# Big_Coil_Gate_Drive_PCBA.net
KiCad netlist of a schematic drawn in Altium Designer
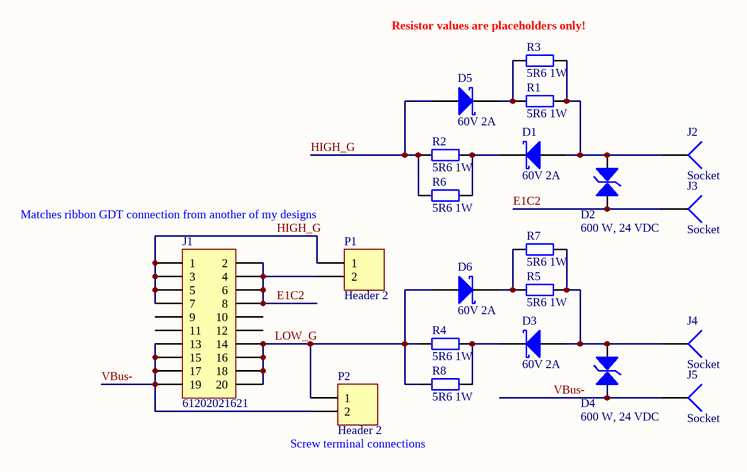
[diagram p0: Big Coil Gate Drive PCBA.SchDoc]

(export (version "E")
  (design (tool "Eeschema 10.0.6"))
  (components
    (comp (ref "D1")
      (value "60V 2A")
      (footprint "DO-214AA_(SMB-J-BEND)_UNI")
      (description "SS26 Schottky rectifier")
      (libsource (lib "TV_Altium_library") (part "SS26"))
    )
    (comp (ref "D2")
      (value "600 W, 24 VDC")
      (footprint "DO-214AA_Bidirectional")
      (description "WE-TVSP Power TVS Diode, bidirectional, 600 W, 24 VDC")
      (fields
        (field (name "PARTNO") "824521241")
        (field (name "MANUFACTURER") "Wurth Elektronik")
        (field (name "CREATED BY") "Baojun Chen")
      )
      (libsource (lib "TV_Altium_library") (part "WE-TVSP DO-214AA, 824521241"))
    )
    (comp (ref "D3")
      (value "60V 2A")
      (footprint "DO-214AA_(SMB-J-BEND)_UNI")
      (description "SS26 Schottky rectifier")
      (libsource (lib "TV_Altium_library") (part "SS26"))
    )
    (comp (ref "D4")
      (value "600 W, 24 VDC")
      (footprint "DO-214AA_Bidirectional")
      (description "WE-TVSP Power TVS Diode, bidirectional, 600 W, 24 VDC")
      (fields
        (field (name "PARTNO") "824521241")
        (field (name "MANUFACTURER") "Wurth Elektronik")
        (field (name "CREATED BY") "Baojun Chen")
      )
      (libsource (lib "TV_Altium_library") (part "WE-TVSP DO-214AA, 824521241"))
    )
    (comp (ref "D5")
      (value "60V 2A")
      (footprint "DO-214AA_(SMB-J-BEND)_UNI")
      (description "SS26 Schottky rectifier")
      (libsource (lib "TV_Altium_library") (part "SS26"))
    )
    (comp (ref "D6")
      (value "60V 2A")
      (footprint "DO-214AA_(SMB-J-BEND)_UNI")
      (description "SS26 Schottky rectifier")
      (libsource (lib "TV_Altium_library") (part "SS26"))
    )
    (comp (ref "J1")
      (value "61202021621")
      (footprint "61202021621")
      (description "WR-BHD 2.54mm Male Box Header")
      (fields (field (name "MANUFACTURER") "Wurth Elektronik") (field (name "CREATED BY") "Baojun Chen"))
      (libsource (lib "TV_Altium_library") (part "61202021621"))
    )
    (comp (ref "J2")
      (value "Socket")
      (footprint "Keystone3534")
      (fields (field (name "PUBLISHER") "Altium Limited"))
      (libsource (lib "Miscellaneous Connectors") (part "Socket"))
    )
    (comp (ref "J3")
      (value "Socket")
      (footprint "Keystone3534")
      (fields (field (name "PUBLISHER") "Altium Limited"))
      (libsource (lib "Miscellaneous Connectors") (part "Socket"))
    )
    (comp (ref "J4")
      (value "Socket")
      (footprint "Keystone3534")
      (fields (field (name "PUBLISHER") "Altium Limited"))
      (libsource (lib "Miscellaneous Connectors") (part "Socket"))
    )
    (comp (ref "J5")
      (value "Socket")
      (footprint "Keystone3534")
      (fields (field (name "PUBLISHER") "Altium Limited"))
      (libsource (lib "Miscellaneous Connectors") (part "Socket"))
    )
    (comp (ref "P1")
      (value "Header 2")
      (footprint "691213510002")
      (description "Header, 2-Pin")
      (fields (field (name "PUBLISHER") "Altium Limited"))
      (libsource (lib "Miscellaneous Connectors") (part "Header 2"))
    )
    (comp (ref "P2")
      (value "Header 2")
      (footprint "691213510002")
      (description "Header, 2-Pin")
      (fields (field (name "PUBLISHER") "Altium Limited"))
      (libsource (lib "Miscellaneous Connectors") (part "Header 2"))
    )
    (comp (ref "R1")
      (value "5R6 1W")
      (description "Resistor")
      (fields (field (name "Comment") "Res2") (field (name "PUBLISHER") "Altium Limited"))
      (libsource (lib "Miscellaneous Devices") (part "Res2"))
    )
    (comp (ref "R2")
      (value "5R6 1W")
      (description "Resistor")
      (fields (field (name "Comment") "Res2") (field (name "PUBLISHER") "Altium Limited"))
      (libsource (lib "Miscellaneous Devices") (part "Res2"))
    )
    (comp (ref "R3")
      (value "5R6 1W")
      (description "Resistor")
      (fields (field (name "Comment") "Res2") (field (name "PUBLISHER") "Altium Limited"))
      (libsource (lib "Miscellaneous Devices") (part "Res2"))
    )
    (comp (ref "R4")
      (value "5R6 1W")
      (description "Resistor")
      (fields (field (name "Comment") "Res2") (field (name "PUBLISHER") "Altium Limited"))
      (libsource (lib "Miscellaneous Devices") (part "Res2"))
    )
    (comp (ref "R5")
      (value "5R6 1W")
      (description "Resistor")
      (fields (field (name "Comment") "Res2") (field (name "PUBLISHER") "Altium Limited"))
      (libsource (lib "Miscellaneous Devices") (part "Res2"))
    )
    (comp (ref "R6")
      (value "5R6 1W")
      (description "Resistor")
      (fields (field (name "Comment") "Res2") (field (name "PUBLISHER") "Altium Limited"))
      (libsource (lib "Miscellaneous Devices") (part "Res2"))
    )
    (comp (ref "R7")
      (value "5R6 1W")
      (description "Resistor")
      (fields (field (name "Comment") "Res2") (field (name "PUBLISHER") "Altium Limited"))
      (libsource (lib "Miscellaneous Devices") (part "Res2"))
    )
    (comp (ref "R8")
      (value "5R6 1W")
      (description "Resistor")
      (fields (field (name "Comment") "Res2") (field (name "PUBLISHER") "Altium Limited"))
      (libsource (lib "Miscellaneous Devices") (part "Res2"))
    )
  )
  (nets
    (net (code "1") (name "/E1C2") (class "Default")
      (node (ref "D2") (pin "2") (pinfunction "2_2") (pintype "passive"))
      (node (ref "J1") (pin "2") (pinfunction "2_2") (pintype "passive"))
      (node (ref "J1") (pin "4") (pinfunction "4_4") (pintype "passive"))
      (node (ref "J1") (pin "6") (pinfunction "6_6") (pintype "passive"))
      (node (ref "J1") (pin "8") (pinfunction "8_8") (pintype "passive"))
      (node (ref "J3") (pin "1") (pinfunction "1_1") (pintype "passive"))
      (node (ref "P1") (pin "2") (pinfunction "2_2") (pintype "passive"))
    )
    (net (code "2") (name "/HIGH_G") (class "Default")
      (node (ref "D5") (pin "A") (pinfunction "A_A") (pintype "passive"))
      (node (ref "J1") (pin "1") (pinfunction "1_1") (pintype "passive"))
      (node (ref "J1") (pin "3") (pinfunction "3_3") (pintype "passive"))
      (node (ref "J1") (pin "5") (pinfunction "5_5") (pintype "passive"))
      (node (ref "J1") (pin "7") (pinfunction "7_7") (pintype "passive"))
      (node (ref "P1") (pin "1") (pinfunction "1_1") (pintype "passive"))
      (node (ref "R2") (pin "1") (pinfunction "1_1") (pintype "passive"))
      (node (ref "R6") (pin "1") (pinfunction "1_1") (pintype "passive"))
    )
    (net (code "3") (name "/LOW_G") (class "Default")
      (node (ref "D6") (pin "A") (pinfunction "A_A") (pintype "passive"))
      (node (ref "J1") (pin "14") (pinfunction "14_14") (pintype "passive"))
      (node (ref "J1") (pin "16") (pinfunction "16_16") (pintype "passive"))
      (node (ref "J1") (pin "18") (pinfunction "18_18") (pintype "passive"))
      (node (ref "J1") (pin "20") (pinfunction "20_20") (pintype "passive"))
      (node (ref "P2") (pin "1") (pinfunction "1_1") (pintype "passive"))
      (node (ref "R4") (pin "1") (pinfunction "1_1") (pintype "passive"))
      (node (ref "R8") (pin "1") (pinfunction "1_1") (pintype "passive"))
    )
    (net (code "4") (name "/VBus-") (class "Default")
      (node (ref "D4") (pin "2") (pinfunction "2_2") (pintype "passive"))
      (node (ref "J1") (pin "13") (pinfunction "13_13") (pintype "passive"))
      (node (ref "J1") (pin "15") (pinfunction "15_15") (pintype "passive"))
      (node (ref "J1") (pin "17") (pinfunction "17_17") (pintype "passive"))
      (node (ref "J1") (pin "19") (pinfunction "19_19") (pintype "passive"))
      (node (ref "J5") (pin "1") (pinfunction "1_1") (pintype "passive"))
      (node (ref "P2") (pin "2") (pinfunction "2_2") (pintype "passive"))
    )
    (net (code "5") (name "Net-(D1-PadA)") (class "Default")
      (node (ref "D1") (pin "A") (pinfunction "A_A") (pintype "passive"))
      (node (ref "D2") (pin "1") (pinfunction "1_1") (pintype "passive"))
      (node (ref "J2") (pin "1") (pinfunction "1_1") (pintype "passive"))
      (node (ref "R1") (pin "2") (pinfunction "2_2") (pintype "passive"))
      (node (ref "R3") (pin "2") (pinfunction "2_2") (pintype "passive"))
    )
    (net (code "6") (name "Net-(D1-PadK)") (class "Default")
      (node (ref "D1") (pin "K") (pinfunction "K_K") (pintype "passive"))
      (node (ref "R2") (pin "2") (pinfunction "2_2") (pintype "passive"))
      (node (ref "R6") (pin "2") (pinfunction "2_2") (pintype "passive"))
    )
    (net (code "7") (name "Net-(D3-PadA)") (class "Default")
      (node (ref "D3") (pin "A") (pinfunction "A_A") (pintype "passive"))
      (node (ref "D4") (pin "1") (pinfunction "1_1") (pintype "passive"))
      (node (ref "J4") (pin "1") (pinfunction "1_1") (pintype "passive"))
      (node (ref "R5") (pin "2") (pinfunction "2_2") (pintype "passive"))
      (node (ref "R7") (pin "2") (pinfunction "2_2") (pintype "passive"))
    )
    (net (code "8") (name "Net-(D3-PadK)") (class "Default")
      (node (ref "D3") (pin "K") (pinfunction "K_K") (pintype "passive"))
      (node (ref "R4") (pin "2") (pinfunction "2_2") (pintype "passive"))
      (node (ref "R8") (pin "2") (pinfunction "2_2") (pintype "passive"))
    )
    (net (code "9") (name "Net-(D5-PadK)") (class "Default")
      (node (ref "D5") (pin "K") (pinfunction "K_K") (pintype "passive"))
      (node (ref "R1") (pin "1") (pinfunction "1_1") (pintype "passive"))
      (node (ref "R3") (pin "1") (pinfunction "1_1") (pintype "passive"))
    )
    (net (code "10") (name "Net-(D6-PadK)") (class "Default")
      (node (ref "D6") (pin "K") (pinfunction "K_K") (pintype "passive"))
      (node (ref "R5") (pin "1") (pinfunction "1_1") (pintype "passive"))
      (node (ref "R7") (pin "1") (pinfunction "1_1") (pintype "passive"))
    )
    (net (code "11") (name "unconnected-(J1-Pad9)") (class "Default")
      (node (ref "J1") (pin "9") (pinfunction "9_9") (pintype "passive"))
    )
    (net (code "12") (name "unconnected-(J1-Pad10)") (class "Default")
      (node (ref "J1") (pin "10") (pinfunction "10_10") (pintype "passive"))
    )
    (net (code "13") (name "unconnected-(J1-Pad11)") (class "Default")
      (node (ref "J1") (pin "11") (pinfunction "11_11") (pintype "passive"))
    )
    (net (code "14") (name "unconnected-(J1-Pad12)") (class "Default")
      (node (ref "J1") (pin "12") (pinfunction "12_12") (pintype "passive"))
    )
  )
)
